# snappergps_1_0_0.net
KiCad netlist of a schematic drawn in EAGLE
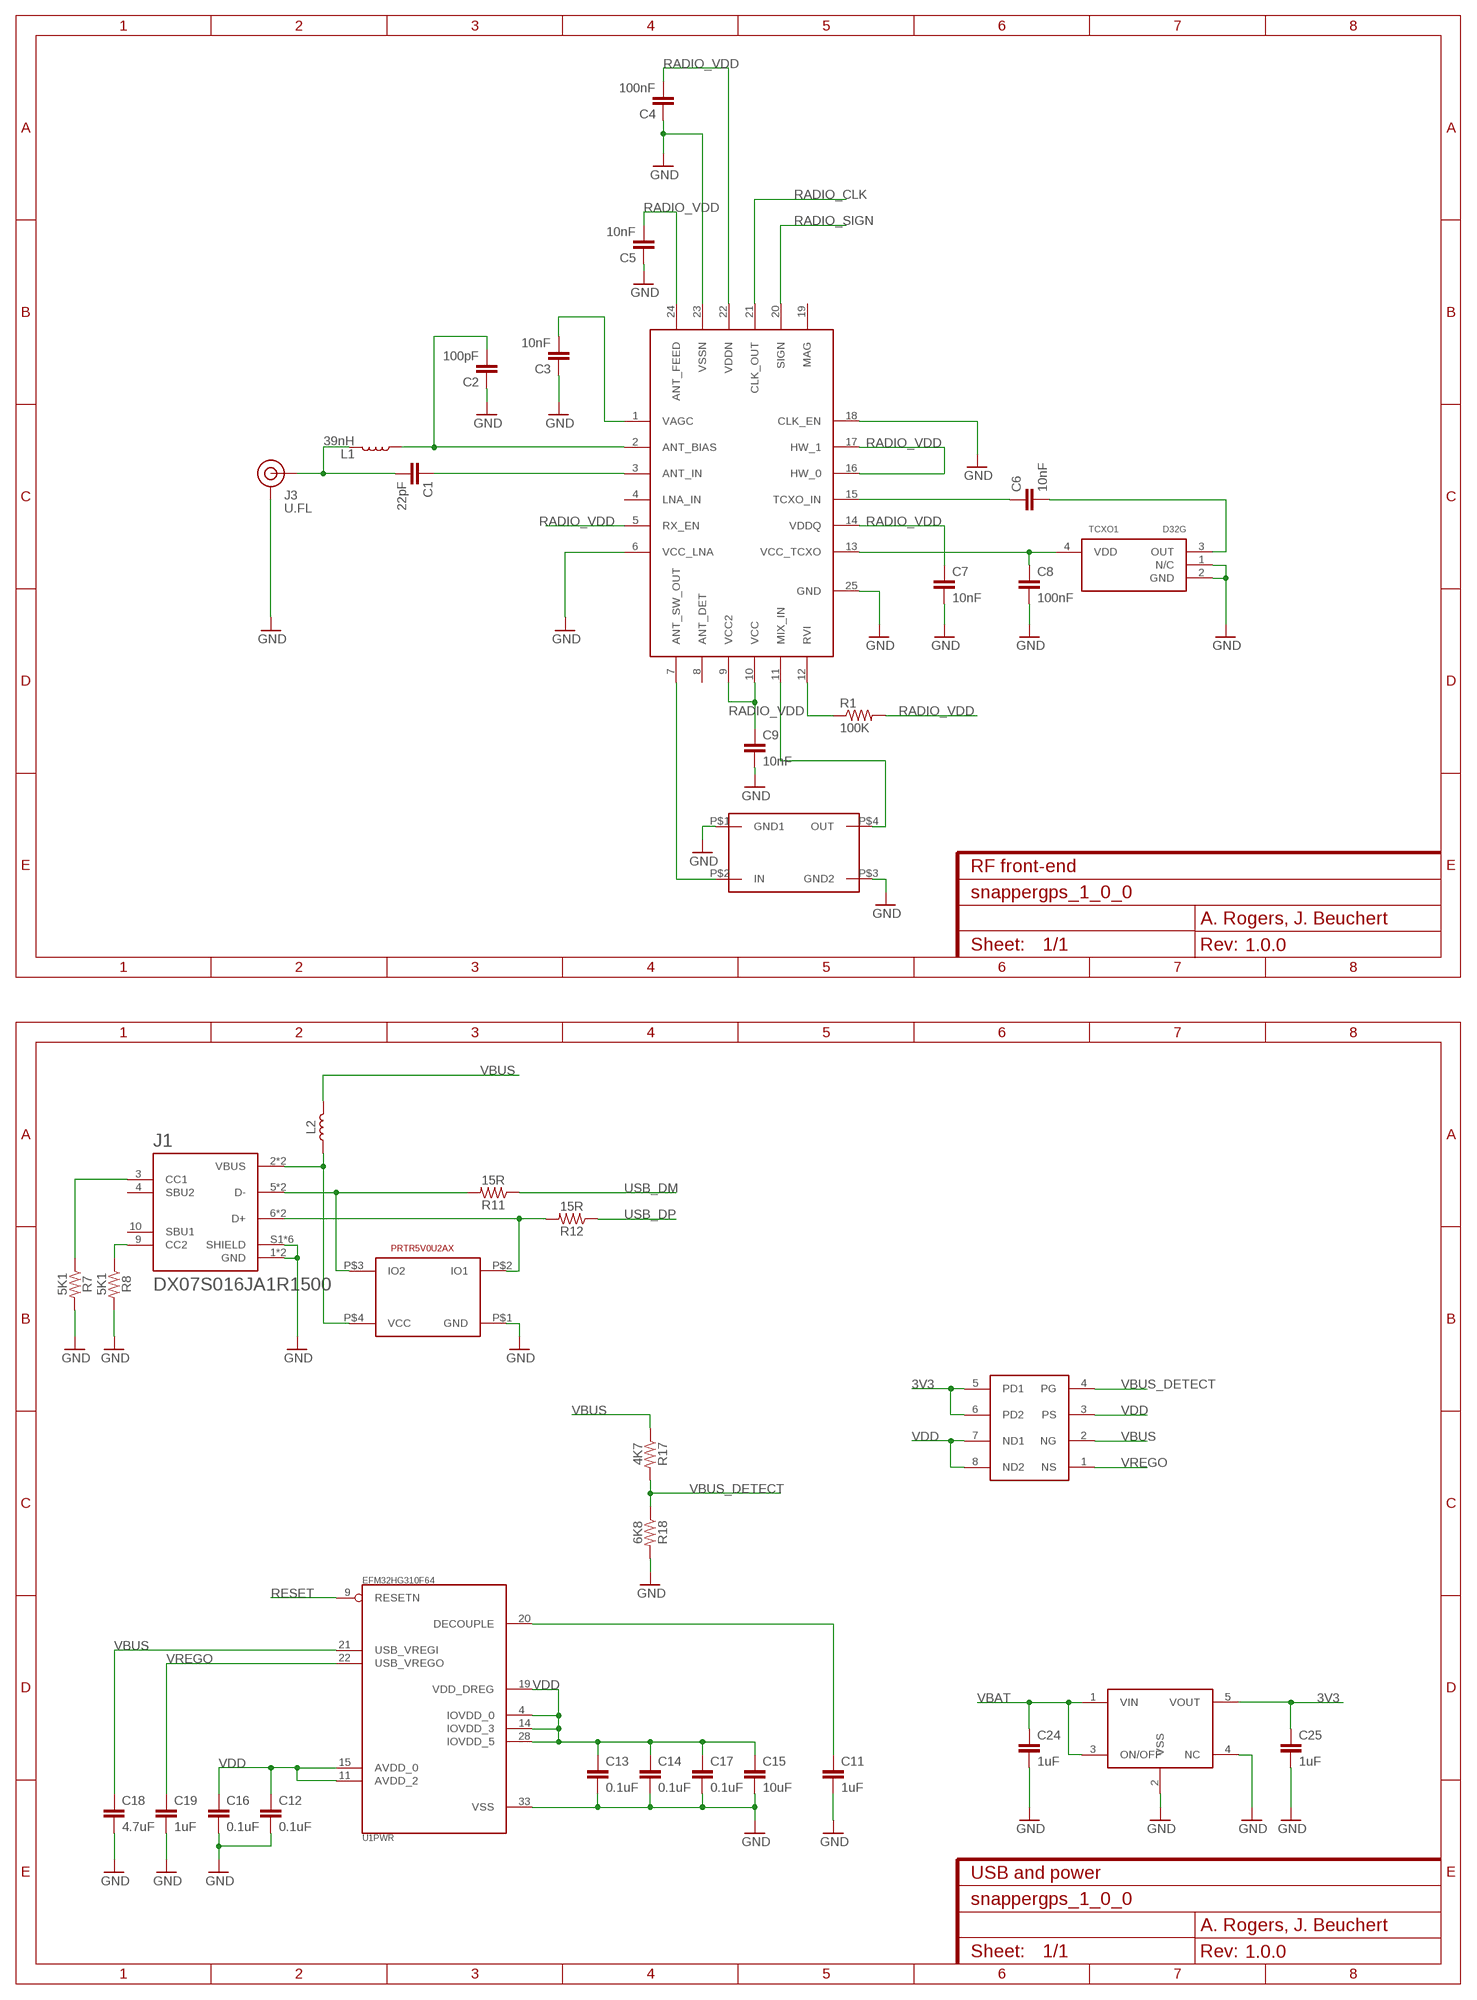
[diagram p0: schematic, sheet 1, part 1 of 2]
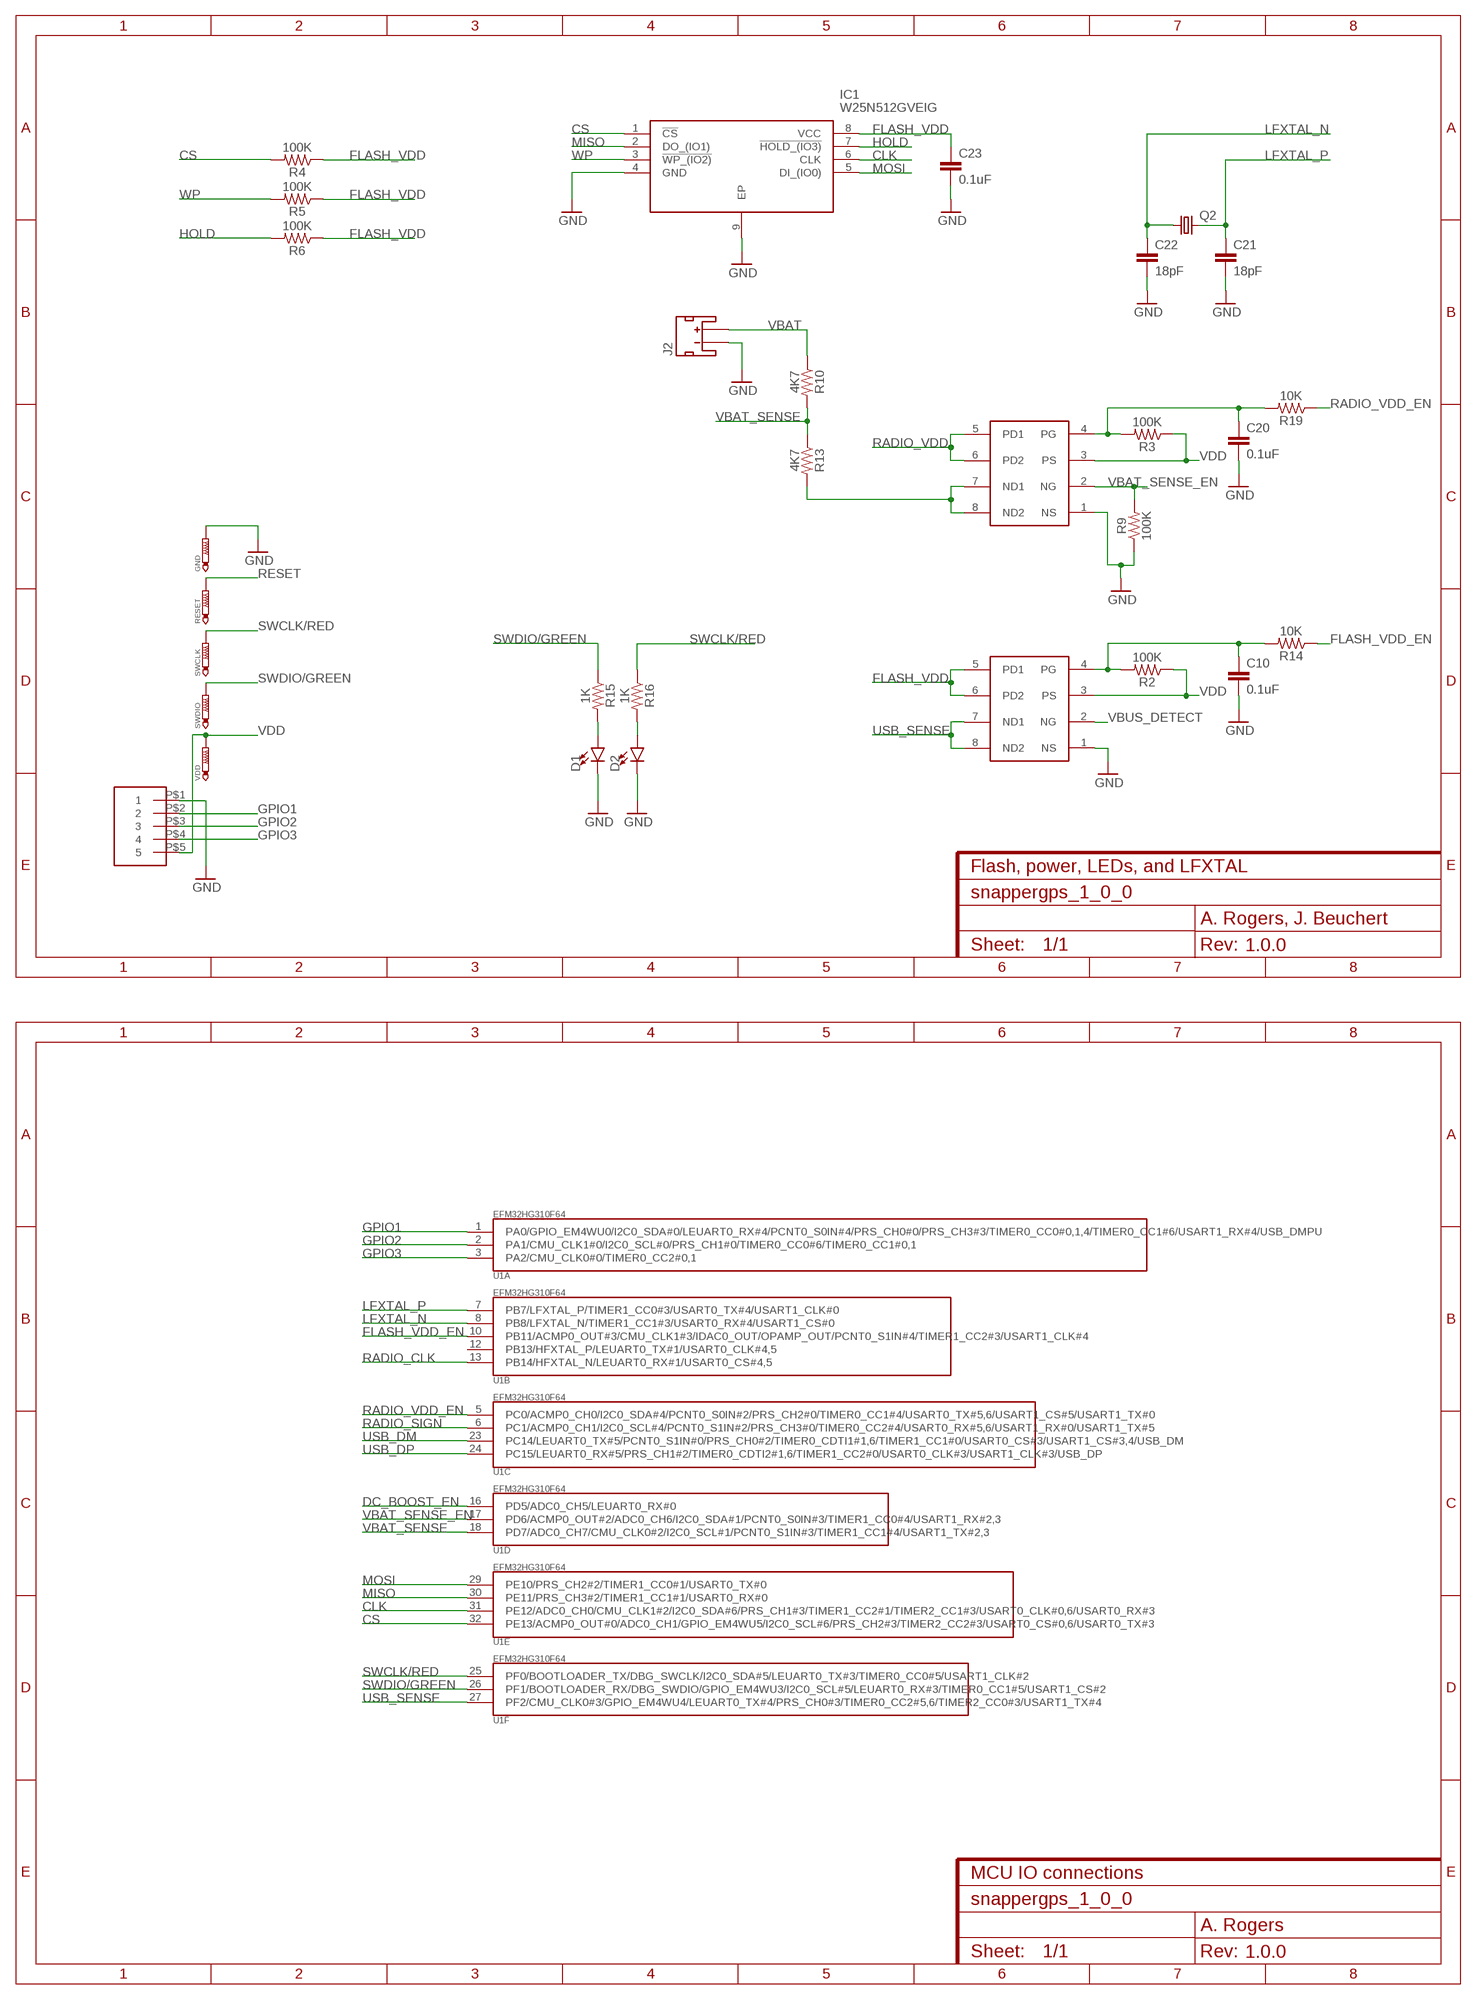
[diagram p1: schematic, sheet 1, part 2 of 2]

(export (version "E")
  (design (tool "Eeschema 10.0.6"))
  (components
    (comp (ref "C1")
      (value "22pF")
      (footprint "eagle-import:0402")
      (libsource (lib "eagle-import") (part "CAPACITOR_0402"))
    )
    (comp (ref "C2")
      (value "100pF")
      (footprint "eagle-import:0402")
      (libsource (lib "eagle-import") (part "CAPACITOR_0402"))
    )
    (comp (ref "C3")
      (value "10nF")
      (footprint "eagle-import:0402")
      (libsource (lib "eagle-import") (part "CAPACITOR_0402"))
    )
    (comp (ref "C4")
      (value "100nF")
      (footprint "eagle-import:0402")
      (libsource (lib "eagle-import") (part "CAPACITOR_0402"))
    )
    (comp (ref "C5")
      (value "10nF")
      (footprint "eagle-import:0402")
      (libsource (lib "eagle-import") (part "CAPACITOR_0402"))
    )
    (comp (ref "C6")
      (value "10nF")
      (footprint "eagle-import:0402")
      (libsource (lib "eagle-import") (part "CAPACITOR_0402"))
    )
    (comp (ref "C7")
      (value "10nF")
      (footprint "eagle-import:0402")
      (libsource (lib "eagle-import") (part "CAPACITOR_0402"))
    )
    (comp (ref "C8")
      (value "100nF")
      (footprint "eagle-import:0402")
      (libsource (lib "eagle-import") (part "CAPACITOR_0402"))
    )
    (comp (ref "C9")
      (value "10nF")
      (footprint "eagle-import:0402")
      (libsource (lib "eagle-import") (part "CAPACITOR_0402"))
    )
    (comp (ref "C10")
      (value "0.1uF")
      (footprint "eagle-import:0402")
      (libsource (lib "eagle-import") (part "CAPACITOR_0402"))
    )
    (comp (ref "C11")
      (value "1uF")
      (footprint "eagle-import:0603")
      (libsource (lib "eagle-import") (part "CAPACITOR_0603"))
    )
    (comp (ref "C12")
      (value "0.1uF")
      (footprint "eagle-import:0402")
      (libsource (lib "eagle-import") (part "CAPACITOR_0402"))
    )
    (comp (ref "C13")
      (value "0.1uF")
      (footprint "eagle-import:0402")
      (libsource (lib "eagle-import") (part "CAPACITOR_0402"))
    )
    (comp (ref "C14")
      (value "0.1uF")
      (footprint "eagle-import:0402")
      (libsource (lib "eagle-import") (part "CAPACITOR_0402"))
    )
    (comp (ref "C15")
      (value "10uF")
      (footprint "eagle-import:0603")
      (libsource (lib "eagle-import") (part "CAPACITOR_0603"))
    )
    (comp (ref "C16")
      (value "0.1uF")
      (footprint "eagle-import:0402")
      (libsource (lib "eagle-import") (part "CAPACITOR_0402"))
    )
    (comp (ref "C17")
      (value "0.1uF")
      (footprint "eagle-import:0402")
      (libsource (lib "eagle-import") (part "CAPACITOR_0402"))
    )
    (comp (ref "C18")
      (value "4.7uF")
      (footprint "eagle-import:0603")
      (libsource (lib "eagle-import") (part "CAPACITOR_0603"))
    )
    (comp (ref "C19")
      (value "1uF")
      (footprint "eagle-import:0603")
      (libsource (lib "eagle-import") (part "CAPACITOR_0603"))
    )
    (comp (ref "C20")
      (value "0.1uF")
      (footprint "eagle-import:0402")
      (libsource (lib "eagle-import") (part "CAPACITOR_0402"))
    )
    (comp (ref "C21")
      (value "18pF")
      (footprint "eagle-import:0402")
      (libsource (lib "eagle-import") (part "CAPACITOR_0402"))
    )
    (comp (ref "C22")
      (value "18pF")
      (footprint "eagle-import:0402")
      (libsource (lib "eagle-import") (part "CAPACITOR_0402"))
    )
    (comp (ref "C23")
      (value "0.1uF")
      (footprint "eagle-import:0402")
      (libsource (lib "eagle-import") (part "CAPACITOR_0402"))
    )
    (comp (ref "C24")
      (value "1uF")
      (footprint "eagle-import:0603")
      (libsource (lib "eagle-import") (part "CAPACITOR_0603"))
    )
    (comp (ref "C25")
      (value "1uF")
      (footprint "eagle-import:0603")
      (libsource (lib "eagle-import") (part "CAPACITOR_0603"))
    )
    (comp (ref "D1")
      (value "LED0603")
      (footprint "eagle-import:LED-0603")
      (libsource (lib "eagle-import") (part "LED0603"))
    )
    (comp (ref "D2")
      (value "LED0603")
      (footprint "eagle-import:LED-0603")
      (libsource (lib "eagle-import") (part "LED0603"))
    )
    (comp (ref "GND")
      (value "PTR1B1,27")
      (footprint "eagle-import:B1,27")
      (libsource (lib "eagle-import") (part "PTR1B1,27"))
    )
    (comp (ref "IC1")
      (value "W25N512GVEIG")
      (footprint "eagle-import:SON127P800X600X80-9N")
      (fields (field (name "MOUSER_PART_NUMBER") "454-W25N512GVEIG"))
      (libsource (lib "eagle-import") (part "W25N512GVEIG"))
    )
    (comp (ref "J1")
      (value "DX07S016JA1R1500")
      (footprint "eagle-import:JAE_DX07S016JA1R1500")
      (fields (field (name "MF") "JAE Electronics"))
      (libsource (lib "eagle-import") (part "DX07S016JA1R1500"))
    )
    (comp (ref "J2")
      (value "JST_2MM_MALE")
      (footprint "eagle-import:JST-2-SMD")
      (libsource (lib "eagle-import") (part "JST_2MM_MALE"))
    )
    (comp (ref "J3")
      (value "U.FL")
      (footprint "eagle-import:U.FL")
      (libsource (lib "eagle-import") (part "UFL-CONNECTOR"))
    )
    (comp (ref "L1")
      (value "39nH")
      (footprint "eagle-import:0402")
      (libsource (lib "eagle-import") (part "INDUCTOR"))
    )
    (comp (ref "L2")
      (value "INDUCTOR")
      (footprint "eagle-import:0402")
      (libsource (lib "eagle-import") (part "INDUCTOR"))
    )
    (comp (ref "Q1")
      (value "TT8M1TRAMANDA")
      (footprint "eagle-import:AMANDA_TSST8")
      (libsource (lib "eagle-import") (part "TT8M1TRAMANDA"))
    )
    (comp (ref "Q2")
      (value "CRYSTAL_JTX310")
      (footprint "eagle-import:3.2X1.5")
      (libsource (lib "eagle-import") (part "CRYSTAL_JTX310"))
    )
    (comp (ref "Q3")
      (value "TT8M1TRAMANDA")
      (footprint "eagle-import:AMANDA_TSST8")
      (libsource (lib "eagle-import") (part "TT8M1TRAMANDA"))
    )
    (comp (ref "Q4")
      (value "TT8M1TRAMANDA")
      (footprint "eagle-import:AMANDA_TSST8")
      (libsource (lib "eagle-import") (part "TT8M1TRAMANDA"))
    )
    (comp (ref "R1")
      (value "100K")
      (footprint "eagle-import:0402")
      (libsource (lib "eagle-import") (part "RESISTOR_0402"))
    )
    (comp (ref "R2")
      (value "100K")
      (footprint "eagle-import:0402")
      (libsource (lib "eagle-import") (part "RESISTOR_0402"))
    )
    (comp (ref "R3")
      (value "100K")
      (footprint "eagle-import:0402")
      (libsource (lib "eagle-import") (part "RESISTOR_0402"))
    )
    (comp (ref "R4")
      (value "100K")
      (footprint "eagle-import:0402")
      (libsource (lib "eagle-import") (part "RESISTOR_0402"))
    )
    (comp (ref "R5")
      (value "100K")
      (footprint "eagle-import:0402")
      (libsource (lib "eagle-import") (part "RESISTOR_0402"))
    )
    (comp (ref "R6")
      (value "100K")
      (footprint "eagle-import:0402")
      (libsource (lib "eagle-import") (part "RESISTOR_0402"))
    )
    (comp (ref "R7")
      (value "5K1")
      (footprint "eagle-import:0402")
      (libsource (lib "eagle-import") (part "RESISTOR_0402"))
    )
    (comp (ref "R8")
      (value "5K1")
      (footprint "eagle-import:0402")
      (libsource (lib "eagle-import") (part "RESISTOR_0402"))
    )
    (comp (ref "R9")
      (value "100K")
      (footprint "eagle-import:0402")
      (libsource (lib "eagle-import") (part "RESISTOR_0402"))
    )
    (comp (ref "R10")
      (value "4K7")
      (footprint "eagle-import:0402")
      (libsource (lib "eagle-import") (part "RESISTOR_0402"))
    )
    (comp (ref "R11")
      (value "15R")
      (footprint "eagle-import:0402")
      (libsource (lib "eagle-import") (part "RESISTOR_0402"))
    )
    (comp (ref "R12")
      (value "15R")
      (footprint "eagle-import:0402")
      (libsource (lib "eagle-import") (part "RESISTOR_0402"))
    )
    (comp (ref "R13")
      (value "4K7")
      (footprint "eagle-import:0402")
      (libsource (lib "eagle-import") (part "RESISTOR_0402"))
    )
    (comp (ref "R14")
      (value "10K")
      (footprint "eagle-import:0402")
      (libsource (lib "eagle-import") (part "RESISTOR_0402"))
    )
    (comp (ref "R15")
      (value "1K")
      (footprint "eagle-import:0402")
      (libsource (lib "eagle-import") (part "RESISTOR_0402"))
    )
    (comp (ref "R16")
      (value "1K")
      (footprint "eagle-import:0402")
      (libsource (lib "eagle-import") (part "RESISTOR_0402"))
    )
    (comp (ref "R17")
      (value "4K7")
      (footprint "eagle-import:0402")
      (libsource (lib "eagle-import") (part "RESISTOR_0402"))
    )
    (comp (ref "R18")
      (value "6K8")
      (footprint "eagle-import:0402")
      (libsource (lib "eagle-import") (part "RESISTOR_0402"))
    )
    (comp (ref "R19")
      (value "10K")
      (footprint "eagle-import:0402")
      (libsource (lib "eagle-import") (part "RESISTOR_0402"))
    )
    (comp (ref "RESET")
      (value "PTR1B1,27")
      (footprint "eagle-import:B1,27")
      (libsource (lib "eagle-import") (part "PTR1B1,27"))
    )
    (comp (ref "SAW1")
      (value "SAW_FILTER")
      (footprint "eagle-import:SAW_FILTER")
      (libsource (lib "eagle-import") (part "SAW_FILTER"))
    )
    (comp (ref "SWCLK")
      (value "PTR1B1,27")
      (footprint "eagle-import:B1,27")
      (libsource (lib "eagle-import") (part "PTR1B1,27"))
    )
    (comp (ref "SWDIO")
      (value "PTR1B1,27")
      (footprint "eagle-import:B1,27")
      (libsource (lib "eagle-import") (part "PTR1B1,27"))
    )
    (comp (ref "TCXO1")
      (value "D32G")
      (footprint "eagle-import:D32G")
      (libsource (lib "eagle-import") (part "D32G"))
    )
    (comp (ref "U1")
      (value "EFM32HG310F64")
      (footprint "eagle-import:QFN32")
      (libsource (lib "eagle-import") (part "EFM32HG310F64"))
    )
    (comp (ref "U2")
      (value "RF_CIRCUIT-SE4150L")
      (footprint "eagle-import:QFN50P400X400X90-25N")
      (libsource (lib "eagle-import") (part "RF_CIRCUIT-SE4150L"))
    )
    (comp (ref "U3")
      (value "TVS_DIODE-PRTR5V0U2AX")
      (footprint "eagle-import:TVS_DIODE-PRTR5V0U2AX")
      (libsource (lib "eagle-import") (part "TVS_DIODE-PRTR5V0U2AX"))
    )
    (comp (ref "U4")
      (value "S-1318D33-M5T1U4")
      (footprint "eagle-import:SOT95P280X145-5N")
      (libsource (lib "eagle-import") (part "S-1318D33-M5T1U4"))
    )
    (comp (ref "U5")
      (value "ALEX_CONN5")
      (footprint "eagle-import:ALEX_CONN5")
      (libsource (lib "eagle-import") (part "ALEX_CONN5"))
    )
    (comp (ref "VDD")
      (value "PTR1B1,27")
      (footprint "eagle-import:B1,27")
      (libsource (lib "eagle-import") (part "PTR1B1,27"))
    )
  )
  (nets
    (net (code "1") (name "/3V3") (class "Default")
      (node (ref "C25") (pin "1") (pinfunction "1_1") (pintype "passive"))
      (node (ref "Q4") (pin "5") (pinfunction "PD1_5") (pintype "bidirectional"))
      (node (ref "Q4") (pin "6") (pinfunction "PD2_6") (pintype "bidirectional"))
      (node (ref "U4") (pin "5") (pinfunction "VOUT_5") (pintype "bidirectional"))
    )
    (net (code "2") (name "/CLK") (class "Default")
      (node (ref "IC1") (pin "6") (pinfunction "CLK_6") (pintype "bidirectional"))
      (node (ref "U1") (pin "31") (pinfunction "PE12/ADC0_CH0/CMU_CLK1#2/I2C0_SDA#6/PRS_CH1#3/TIMER1_CC2#1/TIMER2_CC1#3/USART0_CLK#0,6/USART0_RX#3_31") (pintype "bidirectional"))
    )
    (net (code "3") (name "/CS") (class "Default")
      (node (ref "IC1") (pin "1") (pinfunction "~{CS}_1") (pintype "bidirectional"))
      (node (ref "R4") (pin "2") (pinfunction "2_2") (pintype "passive"))
      (node (ref "U1") (pin "32") (pinfunction "PE13/ACMP0_OUT#0/ADC0_CH1/GPIO_EM4WU5/I2C0_SCL#6/PRS_CH2#3/TIMER2_CC2#3/USART0_CS#0,6/USART0_TX#3_32") (pintype "bidirectional"))
    )
    (net (code "4") (name "/DC_BOOST_EN") (class "Default")
      (node (ref "U1") (pin "16") (pinfunction "PD5/ADC0_CH5/LEUART0_RX#0_16") (pintype "bidirectional"))
    )
    (net (code "5") (name "/FLASH_VDD") (class "Default")
      (node (ref "C23") (pin "1") (pinfunction "1_1") (pintype "passive"))
      (node (ref "IC1") (pin "8") (pinfunction "VCC_8") (pintype "bidirectional"))
      (node (ref "Q3") (pin "5") (pinfunction "PD1_5") (pintype "bidirectional"))
      (node (ref "Q3") (pin "6") (pinfunction "PD2_6") (pintype "bidirectional"))
      (node (ref "R4") (pin "1") (pinfunction "1_1") (pintype "passive"))
      (node (ref "R5") (pin "1") (pinfunction "1_1") (pintype "passive"))
      (node (ref "R6") (pin "1") (pinfunction "1_1") (pintype "passive"))
    )
    (net (code "6") (name "/FLASH_VDD_EN") (class "Default")
      (node (ref "R14") (pin "1") (pinfunction "1_1") (pintype "passive"))
      (node (ref "U1") (pin "10") (pinfunction "PB11/ACMP0_OUT#3/CMU_CLK1#3/IDAC0_OUT/OPAMP_OUT/PCNT0_S1IN#4/TIMER1_CC2#3/USART1_CLK#4_10") (pintype "bidirectional"))
    )
    (net (code "7") (name "/GPIO1") (class "Default")
      (node (ref "U1") (pin "1") (pinfunction "PA0/GPIO_EM4WU0/I2C0_SDA#0/LEUART0_RX#4/PCNT0_S0IN#4/PRS_CH0#0/PRS_CH3#3/TIMER0_CC0#0,1,4/TIMER0_CC1#6/USART1_RX#4/USB_DMPU_1") (pintype "bidirectional"))
      (node (ref "U5") (pin "P$2") (pinfunction "2_P$2") (pintype "bidirectional"))
    )
    (net (code "8") (name "/GPIO2") (class "Default")
      (node (ref "U1") (pin "2") (pinfunction "PA1/CMU_CLK1#0/I2C0_SCL#0/PRS_CH1#0/TIMER0_CC0#6/TIMER0_CC1#0,1_2") (pintype "bidirectional"))
      (node (ref "U5") (pin "P$3") (pinfunction "3_P$3") (pintype "bidirectional"))
    )
    (net (code "9") (name "/GPIO3") (class "Default")
      (node (ref "U1") (pin "3") (pinfunction "PA2/CMU_CLK0#0/TIMER0_CC2#0,1_3") (pintype "bidirectional"))
      (node (ref "U5") (pin "P$4") (pinfunction "4_P$4") (pintype "bidirectional"))
    )
    (net (code "10") (name "/HOLD") (class "Default")
      (node (ref "IC1") (pin "7") (pinfunction "~{HOLD_(IO3})_7") (pintype "bidirectional"))
      (node (ref "R6") (pin "2") (pinfunction "2_2") (pintype "passive"))
    )
    (net (code "11") (name "/LFXTAL_N") (class "Default")
      (node (ref "C22") (pin "1") (pinfunction "1_1") (pintype "passive"))
      (node (ref "Q2") (pin "1") (pinfunction "1_1") (pintype "passive"))
      (node (ref "U1") (pin "8") (pinfunction "PB8/LFXTAL_N/TIMER1_CC1#3/USART0_RX#4/USART1_CS#0_8") (pintype "bidirectional"))
    )
    (net (code "12") (name "/LFXTAL_P") (class "Default")
      (node (ref "C21") (pin "1") (pinfunction "1_1") (pintype "passive"))
      (node (ref "Q2") (pin "2") (pinfunction "2_2") (pintype "passive"))
      (node (ref "U1") (pin "7") (pinfunction "PB7/LFXTAL_P/TIMER1_CC0#3/USART0_TX#4/USART1_CLK#0_7") (pintype "bidirectional"))
    )
    (net (code "13") (name "/MISO") (class "Default")
      (node (ref "IC1") (pin "2") (pinfunction "DO_(IO1)_2") (pintype "bidirectional"))
      (node (ref "U1") (pin "30") (pinfunction "PE11/PRS_CH3#2/TIMER1_CC1#1/USART0_RX#0_30") (pintype "bidirectional"))
    )
    (net (code "14") (name "/MOSI") (class "Default")
      (node (ref "IC1") (pin "5") (pinfunction "DI_(IO0)_5") (pintype "bidirectional"))
      (node (ref "U1") (pin "29") (pinfunction "PE10/PRS_CH2#2/TIMER1_CC0#1/USART0_TX#0_29") (pintype "bidirectional"))
    )
    (net (code "15") (name "/RADIO_CLK") (class "Default")
      (node (ref "U1") (pin "13") (pinfunction "PB14/HFXTAL_N/LEUART0_RX#1/USART0_CS#4,5_13") (pintype "bidirectional"))
      (node (ref "U2") (pin "21") (pinfunction "CLK_OUT_21") (pintype "bidirectional"))
    )
    (net (code "16") (name "/RADIO_SIGN") (class "Default")
      (node (ref "U1") (pin "6") (pinfunction "PC1/ACMP0_CH1/I2C0_SCL#4/PCNT0_S1IN#2/PRS_CH3#0/TIMER0_CC2#4/USART0_RX#5,6/USART1_RX#0/USART1_TX#5_6") (pintype "bidirectional"))
      (node (ref "U2") (pin "20") (pinfunction "SIGN_20") (pintype "bidirectional"))
    )
    (net (code "17") (name "/RADIO_VDD") (class "Default")
      (node (ref "C4") (pin "2") (pinfunction "2_2") (pintype "passive"))
      (node (ref "C5") (pin "2") (pinfunction "2_2") (pintype "passive"))
      (node (ref "C7") (pin "1") (pinfunction "1_1") (pintype "passive"))
      (node (ref "C9") (pin "1") (pinfunction "1_1") (pintype "passive"))
      (node (ref "Q1") (pin "5") (pinfunction "PD1_5") (pintype "bidirectional"))
      (node (ref "Q1") (pin "6") (pinfunction "PD2_6") (pintype "bidirectional"))
      (node (ref "R1") (pin "2") (pinfunction "2_2") (pintype "passive"))
      (node (ref "U2") (pin "10") (pinfunction "VCC_10") (pintype "bidirectional"))
      (node (ref "U2") (pin "14") (pinfunction "VDDQ_14") (pintype "bidirectional"))
      (node (ref "U2") (pin "16") (pinfunction "HW_0_16") (pintype "bidirectional"))
      (node (ref "U2") (pin "17") (pinfunction "HW_1_17") (pintype "bidirectional"))
      (node (ref "U2") (pin "22") (pinfunction "VDDN_22") (pintype "bidirectional"))
      (node (ref "U2") (pin "24") (pinfunction "ANT_FEED_24") (pintype "bidirectional"))
      (node (ref "U2") (pin "5") (pinfunction "RX_EN_5") (pintype "bidirectional"))
      (node (ref "U2") (pin "9") (pinfunction "VCC2_9") (pintype "bidirectional"))
    )
    (net (code "18") (name "/RADIO_VDD_EN") (class "Default")
      (node (ref "R19") (pin "1") (pinfunction "1_1") (pintype "passive"))
      (node (ref "U1") (pin "5") (pinfunction "PC0/ACMP0_CH0/I2C0_SDA#4/PCNT0_S0IN#2/PRS_CH2#0/TIMER0_CC1#4/USART0_TX#5,6/USART1_CS#5/USART1_TX#0_5") (pintype "bidirectional"))
    )
    (net (code "19") (name "/RESET") (class "Default")
      (node (ref "RESET") (pin "TP") (pinfunction "TP_TP") (pintype "input"))
      (node (ref "U1") (pin "9") (pinfunction "RESETN_9") (pintype "passive"))
    )
    (net (code "20") (name "/SWCLK{slash}RED") (class "Default")
      (node (ref "R16") (pin "1") (pinfunction "1_1") (pintype "passive"))
      (node (ref "SWCLK") (pin "TP") (pinfunction "TP_TP") (pintype "input"))
      (node (ref "U1") (pin "25") (pinfunction "PF0/BOOTLOADER_TX/DBG_SWCLK/I2C0_SDA#5/LEUART0_TX#3/TIMER0_CC0#5/USART1_CLK#2_25") (pintype "bidirectional"))
    )
    (net (code "21") (name "/SWDIO{slash}GREEN") (class "Default")
      (node (ref "R15") (pin "1") (pinfunction "1_1") (pintype "passive"))
      (node (ref "SWDIO") (pin "TP") (pinfunction "TP_TP") (pintype "input"))
      (node (ref "U1") (pin "26") (pinfunction "PF1/BOOTLOADER_RX/DBG_SWDIO/GPIO_EM4WU3/I2C0_SCL#5/LEUART0_RX#3/TIMER0_CC1#5/USART1_CS#2_26") (pintype "bidirectional"))
    )
    (net (code "22") (name "/USB_DM") (class "Default")
      (node (ref "R11") (pin "1") (pinfunction "1_1") (pintype "passive"))
      (node (ref "U1") (pin "23") (pinfunction "PC14/LEUART0_TX#5/PCNT0_S1IN#0/PRS_CH0#2/TIMER0_CDTI1#1,6/TIMER1_CC1#0/USART0_CS#3/USART1_CS#3,4/USB_DM_23") (pintype "bidirectional"))
    )
    (net (code "23") (name "/USB_DP") (class "Default")
      (node (ref "R12") (pin "1") (pinfunction "1_1") (pintype "passive"))
      (node (ref "U1") (pin "24") (pinfunction "PC15/LEUART0_RX#5/PRS_CH1#2/TIMER0_CDTI2#1,6/TIMER1_CC2#0/USART0_CLK#3/USART1_CLK#3/USB_DP_24") (pintype "bidirectional"))
    )
    (net (code "24") (name "/USB_SENSE") (class "Default")
      (node (ref "Q3") (pin "7") (pinfunction "ND1_7") (pintype "bidirectional"))
      (node (ref "Q3") (pin "8") (pinfunction "ND2_8") (pintype "bidirectional"))
      (node (ref "U1") (pin "27") (pinfunction "PF2/CMU_CLK0#3/GPIO_EM4WU4/LEUART0_TX#4/PRS_CH0#3/TIMER0_CC2#5,6/TIMER2_CC0#3/USART1_TX#4_27") (pintype "bidirectional"))
    )
    (net (code "25") (name "/VBAT") (class "Default")
      (node (ref "C24") (pin "1") (pinfunction "1_1") (pintype "passive"))
      (node (ref "J2") (pin "2") (pinfunction "+_2") (pintype "bidirectional"))
      (node (ref "R10") (pin "1") (pinfunction "1_1") (pintype "passive"))
      (node (ref "U4") (pin "1") (pinfunction "VIN_1") (pintype "bidirectional"))
      (node (ref "U4") (pin "3") (pinfunction "ON/OFF_3") (pintype "bidirectional"))
    )
    (net (code "26") (name "/VBAT_SENSE") (class "Default")
      (node (ref "R10") (pin "2") (pinfunction "2_2") (pintype "passive"))
      (node (ref "R13") (pin "1") (pinfunction "1_1") (pintype "passive"))
      (node (ref "U1") (pin "18") (pinfunction "PD7/ADC0_CH7/CMU_CLK0#2/I2C0_SCL#1/PCNT0_S1IN#3/TIMER1_CC1#4/USART1_TX#2,3_18") (pintype "bidirectional"))
    )
    (net (code "27") (name "/VBAT_SENSE_EN") (class "Default")
      (node (ref "Q1") (pin "2") (pinfunction "NG_2") (pintype "bidirectional"))
      (node (ref "R9") (pin "2") (pinfunction "2_2") (pintype "passive"))
      (node (ref "U1") (pin "17") (pinfunction "PD6/ACMP0_OUT#2/ADC0_CH6/I2C0_SDA#1/PCNT0_S0IN#3/TIMER1_CC0#4/USART1_RX#2,3_17") (pintype "bidirectional"))
    )
    (net (code "28") (name "/VBUS") (class "Default")
      (node (ref "C18") (pin "1") (pinfunction "1_1") (pintype "passive"))
      (node (ref "L2") (pin "2") (pinfunction "2_2") (pintype "passive"))
      (node (ref "Q4") (pin "2") (pinfunction "NG_2") (pintype "bidirectional"))
      (node (ref "R17") (pin "1") (pinfunction "1_1") (pintype "passive"))
      (node (ref "U1") (pin "21") (pinfunction "USB_VREGI_21") (pintype "power_in"))
    )
    (net (code "29") (name "/VBUS_DETECT") (class "Default")
      (node (ref "Q3") (pin "2") (pinfunction "NG_2") (pintype "bidirectional"))
      (node (ref "Q4") (pin "4") (pinfunction "PG_4") (pintype "bidirectional"))
      (node (ref "R17") (pin "2") (pinfunction "2_2") (pintype "passive"))
      (node (ref "R18") (pin "1") (pinfunction "1_1") (pintype "passive"))
    )
    (net (code "30") (name "/VDD") (class "Default")
      (node (ref "C12") (pin "1") (pinfunction "1_1") (pintype "passive"))
      (node (ref "C13") (pin "1") (pinfunction "1_1") (pintype "passive"))
      (node (ref "C14") (pin "1") (pinfunction "1_1") (pintype "passive"))
      (node (ref "C15") (pin "1") (pinfunction "1_1") (pintype "passive"))
      (node (ref "C16") (pin "1") (pinfunction "1_1") (pintype "passive"))
      (node (ref "C17") (pin "1") (pinfunction "1_1") (pintype "passive"))
      (node (ref "Q1") (pin "3") (pinfunction "PS_3") (pintype "bidirectional"))
      (node (ref "Q3") (pin "3") (pinfunction "PS_3") (pintype "bidirectional"))
      (node (ref "Q4") (pin "3") (pinfunction "PS_3") (pintype "bidirectional"))
      (node (ref "Q4") (pin "7") (pinfunction "ND1_7") (pintype "bidirectional"))
      (node (ref "Q4") (pin "8") (pinfunction "ND2_8") (pintype "bidirectional"))
      (node (ref "R2") (pin "1") (pinfunction "1_1") (pintype "passive"))
      (node (ref "R3") (pin "1") (pinfunction "1_1") (pintype "passive"))
      (node (ref "U1") (pin "11") (pinfunction "AVDD_2_11") (pintype "power_in"))
      (node (ref "U1") (pin "14") (pinfunction "IOVDD_3_14") (pintype "power_in"))
      (node (ref "U1") (pin "15") (pinfunction "AVDD_0_15") (pintype "power_in"))
      (node (ref "U1") (pin "19") (pinfunction "VDD_DREG_19") (pintype "power_in"))
      (node (ref "U1") (pin "28") (pinfunction "IOVDD_5_28") (pintype "power_in"))
      (node (ref "U1") (pin "4") (pinfunction "IOVDD_0_4") (pintype "power_in"))
      (node (ref "U5") (pin "P$5") (pinfunction "5_P$5") (pintype "bidirectional"))
      (node (ref "VDD") (pin "TP") (pinfunction "TP_TP") (pintype "input"))
    )
    (net (code "31") (name "/VREGO") (class "Default")
      (node (ref "C19") (pin "1") (pinfunction "1_1") (pintype "passive"))
      (node (ref "Q4") (pin "1") (pinfunction "NS_1") (pintype "bidirectional"))
      (node (ref "U1") (pin "22") (pinfunction "USB_VREGO_22") (pintype "power_in"))
    )
    (net (code "32") (name "/WP") (class "Default")
      (node (ref "IC1") (pin "3") (pinfunction "~{WP_(IO2})_3") (pintype "bidirectional"))
      (node (ref "R5") (pin "2") (pinfunction "2_2") (pintype "passive"))
    )
    (net (code "33") (name "GND") (class "Default")
      (node (ref "C10") (pin "2") (pinfunction "2_2") (pintype "passive"))
      (node (ref "C11") (pin "2") (pinfunction "2_2") (pintype "passive"))
      (node (ref "C12") (pin "2") (pinfunction "2_2") (pintype "passive"))
      (node (ref "C13") (pin "2") (pinfunction "2_2") (pintype "passive"))
      (node (ref "C14") (pin "2") (pinfunction "2_2") (pintype "passive"))
      (node (ref "C15") (pin "2") (pinfunction "2_2") (pintype "passive"))
      (node (ref "C16") (pin "2") (pinfunction "2_2") (pintype "passive"))
      (node (ref "C17") (pin "2") (pinfunction "2_2") (pintype "passive"))
      (node (ref "C18") (pin "2") (pinfunction "2_2") (pintype "passive"))
      (node (ref "C19") (pin "2") (pinfunction "2_2") (pintype "passive"))
      (node (ref "C2") (pin "1") (pinfunction "1_1") (pintype "passive"))
      (node (ref "C20") (pin "2") (pinfunction "2_2") (pintype "passive"))
      (node (ref "C21") (pin "2") (pinfunction "2_2") (pintype "passive"))
      (node (ref "C22") (pin "2") (pinfunction "2_2") (pintype "passive"))
      (node (ref "C23") (pin "2") (pinfunction "2_2") (pintype "passive"))
      (node (ref "C24") (pin "2") (pinfunction "2_2") (pintype "passive"))
      (node (ref "C25") (pin "2") (pinfunction "2_2") (pintype "passive"))
      (node (ref "C3") (pin "1") (pinfunction "1_1") (pintype "passive"))
      (node (ref "C4") (pin "1") (pinfunction "1_1") (pintype "passive"))
      (node (ref "C5") (pin "1") (pinfunction "1_1") (pintype "passive"))
      (node (ref "C7") (pin "2") (pinfunction "2_2") (pintype "passive"))
      (node (ref "C8") (pin "2") (pinfunction "2_2") (pintype "passive"))
      (node (ref "C9") (pin "2") (pinfunction "2_2") (pintype "passive"))
      (node (ref "D1") (pin "C") (pinfunction "C_C") (pintype "passive"))
      (node (ref "D2") (pin "C") (pinfunction "C_C") (pintype "passive"))
      (node (ref "GND") (pin "TP") (pinfunction "TP_TP") (pintype "input"))
      (node (ref "IC1") (pin "4") (pinfunction "GND_4") (pintype "bidirectional"))
      (node (ref "IC1") (pin "9") (pinfunction "EP_9") (pintype "bidirectional"))
      (node (ref "J1") (pin "1") (pinfunction "GND_1") (pintype "power_in"))
      (node (ref "J1") (pin "12") (pinfunction "GND_12") (pintype "power_in"))
      (node (ref "J1") (pin "S1") (pinfunction "SHIELD_S1") (pintype "passive"))
      (node (ref "J1") (pin "S2") (pinfunction "SHIELD_S2") (pintype "passive"))
      (node (ref "J1") (pin "S3") (pinfunction "SHIELD_S3") (pintype "passive"))
      (node (ref "J1") (pin "S4") (pinfunction "SHIELD_S4") (pintype "passive"))
      (node (ref "J1") (pin "S5") (pinfunction "SHIELD_S5") (pintype "passive"))
      (node (ref "J1") (pin "S6") (pinfunction "SHIELD_S6") (pintype "passive"))
      (node (ref "J2") (pin "1") (pinfunction "-_1") (pintype "bidirectional"))
      (node (ref "J3") (pin "1") (pinfunction "GND_1") (pintype "bidirectional"))
      (node (ref "J3") (pin "2") (pinfunction "GND_2") (pintype "bidirectional"))
      (node (ref "Q1") (pin "1") (pinfunction "NS_1") (pintype "bidirectional"))
      (node (ref "Q3") (pin "1") (pinfunction "NS_1") (pintype "bidirectional"))
      (node (ref "R18") (pin "2") (pinfunction "2_2") (pintype "passive"))
      (node (ref "R7") (pin "2") (pinfunction "2_2") (pintype "passive"))
      (node (ref "R8") (pin "2") (pinfunction "2_2") (pintype "passive"))
      (node (ref "R9") (pin "1") (pinfunction "1_1") (pintype "passive"))
      (node (ref "SAW1") (pin "P$1") (pinfunction "GND1_P$1") (pintype "bidirectional"))
      (node (ref "SAW1") (pin "P$3") (pinfunction "GND2_P$3") (pintype "bidirectional"))
      (node (ref "TCXO1") (pin "1") (pinfunction "N/C_1") (pintype "bidirectional"))
      (node (ref "TCXO1") (pin "2") (pinfunction "GND_2") (pintype "bidirectional"))
      (node (ref "U1") (pin "33") (pinfunction "VSS_33") (pintype "power_in"))
      (node (ref "U2") (pin "18") (pinfunction "CLK_EN_18") (pintype "bidirectional"))
      (node (ref "U2") (pin "23") (pinfunction "VSSN_23") (pintype "bidirectional"))
      (node (ref "U2") (pin "25") (pinfunction "GND_25") (pintype "bidirectional"))
      (node (ref "U2") (pin "6") (pinfunction "VCC_LNA_6") (pintype "bidirectional"))
      (node (ref "U3") (pin "P$1") (pinfunction "GND_P$1") (pintype "bidirectional"))
      (node (ref "U4") (pin "2") (pinfunction "VSS_2") (pintype "bidirectional"))
      (node (ref "U4") (pin "4") (pinfunction "NC_4") (pintype "bidirectional"))
      (node (ref "U5") (pin "P$1") (pinfunction "1_P$1") (pintype "bidirectional"))
    )
    (net (code "34") (name "Net-(D1-PadA)") (class "Default")
      (node (ref "D1") (pin "A") (pinfunction "A_A") (pintype "passive"))
      (node (ref "R15") (pin "2") (pinfunction "2_2") (pintype "passive"))
    )
    (net (code "35") (name "Net-(D2-PadA)") (class "Default")
      (node (ref "D2") (pin "A") (pinfunction "A_A") (pintype "passive"))
      (node (ref "R16") (pin "2") (pinfunction "2_2") (pintype "passive"))
    )
    (net (code "36") (name "Net-(J1-CC1)") (class "Default")
      (node (ref "J1") (pin "3") (pinfunction "CC1_3") (pintype "passive"))
      (node (ref "R7") (pin "1") (pinfunction "1_1") (pintype "passive"))
    )
    (net (code "37") (name "Net-(J1-CC2)") (class "Default")
      (node (ref "J1") (pin "9") (pinfunction "CC2_9") (pintype "passive"))
      (node (ref "R8") (pin "1") (pinfunction "1_1") (pintype "passive"))
    )
    (net (code "38") (name "Net-(J3-SIGNAL)") (class "Default")
      (node (ref "C1") (pin "2") (pinfunction "2_2") (pintype "passive"))
      (node (ref "J3") (pin "FEED") (pinfunction "SIGNAL_FEED") (pintype "bidirectional"))
      (node (ref "L1") (pin "2") (pinfunction "2_2") (pintype "passive"))
    )
    (net (code "39") (name "Net-(Q1-ND1)") (class "Default")
      (node (ref "Q1") (pin "7") (pinfunction "ND1_7") (pintype "bidirectional"))
      (node (ref "Q1") (pin "8") (pinfunction "ND2_8") (pintype "bidirectional"))
      (node (ref "R13") (pin "2") (pinfunction "2_2") (pintype "passive"))
    )
    (net (code "40") (name "Net-(Q1-PG)") (class "Default")
      (node (ref "C20") (pin "1") (pinfunction "1_1") (pintype "passive"))
      (node (ref "Q1") (pin "4") (pinfunction "PG_4") (pintype "bidirectional"))
      (node (ref "R19") (pin "2") (pinfunction "2_2") (pintype "passive"))
      (node (ref "R3") (pin "2") (pinfunction "2_2") (pintype "passive"))
    )
    (net (code "41") (name "Net-(Q3-PG)") (class "Default")
      (node (ref "C10") (pin "1") (pinfunction "1_1") (pintype "passive"))
      (node (ref "Q3") (pin "4") (pinfunction "PG_4") (pintype "bidirectional"))
      (node (ref "R14") (pin "2") (pinfunction "2_2") (pintype "passive"))
      (node (ref "R2") (pin "2") (pinfunction "2_2") (pintype "passive"))
    )
    (net (code "42") (name "Net-(SAW1-IN)") (class "Default")
      (node (ref "SAW1") (pin "P$2") (pinfunction "IN_P$2") (pintype "bidirectional"))
      (node (ref "U2") (pin "7") (pinfunction "ANT_SW_OUT_7") (pintype "bidirectional"))
    )
    (net (code "43") (name "Net-(SAW1-OUT)") (class "Default")
      (node (ref "SAW1") (pin "P$4") (pinfunction "OUT_P$4") (pintype "bidirectional"))
      (node (ref "U2") (pin "11") (pinfunction "MIX_IN_11") (pintype "bidirectional"))
    )
    (net (code "44") (name "Net-(TCXO1-OUT)") (class "Default")
      (node (ref "C6") (pin "2") (pinfunction "2_2") (pintype "passive"))
      (node (ref "TCXO1") (pin "3") (pinfunction "OUT_3") (pintype "bidirectional"))
    )
    (net (code "45") (name "Net-(TCXO1-VDD)") (class "Default")
      (node (ref "C8") (pin "1") (pinfunction "1_1") (pintype "passive"))
      (node (ref "TCXO1") (pin "4") (pinfunction "VDD_4") (pintype "bidirectional"))
      (node (ref "U2") (pin "13") (pinfunction "VCC_TCXO_13") (pintype "bidirectional"))
    )
    (net (code "46") (name "Net-(U1G-DECOUPLE)") (class "Default")
      (node (ref "C11") (pin "1") (pinfunction "1_1") (pintype "passive"))
      (node (ref "U1") (pin "20") (pinfunction "DECOUPLE_20") (pintype "power_in"))
    )
    (net (code "47") (name "Net-(U2-ANT_BIAS)") (class "Default")
      (node (ref "C2") (pin "2") (pinfunction "2_2") (pintype "passive"))
      (node (ref "L1") (pin "1") (pinfunction "1_1") (pintype "passive"))
      (node (ref "U2") (pin "2") (pinfunction "ANT_BIAS_2") (pintype "bidirectional"))
    )
    (net (code "48") (name "Net-(U2-ANT_IN)") (class "Default")
      (node (ref "C1") (pin "1") (pinfunction "1_1") (pintype "passive"))
      (node (ref "U2") (pin "3") (pinfunction "ANT_IN_3") (pintype "bidirectional"))
    )
    (net (code "49") (name "Net-(U2-RVI)") (class "Default")
      (node (ref "R1") (pin "1") (pinfunction "1_1") (pintype "passive"))
      (node (ref "U2") (pin "12") (pinfunction "RVI_12") (pintype "bidirectional"))
    )
    (net (code "50") (name "Net-(U2-TCXO_IN)") (class "Default")
      (node (ref "C6") (pin "1") (pinfunction "1_1") (pintype "passive"))
      (node (ref "U2") (pin "15") (pinfunction "TCXO_IN_15") (pintype "bidirectional"))
    )
    (net (code "51") (name "Net-(U2-VAGC)") (class "Default")
      (node (ref "C3") (pin "2") (pinfunction "2_2") (pintype "passive"))
      (node (ref "U2") (pin "1") (pinfunction "VAGC_1") (pintype "bidirectional"))
    )
    (net (code "52") (name "Net-(U3-IO1)") (class "Default")
      (node (ref "J1") (pin "6") (pinfunction "D+_6") (pintype "passive"))
      (node (ref "J1") (pin "7") (pinfunction "D+_7") (pintype "passive"))
      (node (ref "R12") (pin "2") (pinfunction "2_2") (pintype "passive"))
      (node (ref "U3") (pin "P$2") (pinfunction "IO1_P$2") (pintype "bidirectional"))
    )
    (net (code "53") (name "Net-(U3-IO2)") (class "Default")
      (node (ref "J1") (pin "5") (pinfunction "D-_5") (pintype "passive"))
      (node (ref "J1") (pin "8") (pinfunction "D-_8") (pintype "passive"))
      (node (ref "R11") (pin "2") (pinfunction "2_2") (pintype "passive"))
      (node (ref "U3") (pin "P$3") (pinfunction "IO2_P$3") (pintype "bidirectional"))
    )
    (net (code "54") (name "Net-(U3-VCC)") (class "Default")
      (node (ref "J1") (pin "11") (pinfunction "VBUS_11") (pintype "power_in"))
      (node (ref "J1") (pin "2") (pinfunction "VBUS_2") (pintype "power_in"))
      (node (ref "L2") (pin "1") (pinfunction "1_1") (pintype "passive"))
      (node (ref "U3") (pin "P$4") (pinfunction "VCC_P$4") (pintype "bidirectional"))
    )
    (net (code "55") (name "unconnected-(J1-SBU1-Pad10)") (class "Default")
      (node (ref "J1") (pin "10") (pinfunction "SBU1_10") (pintype "passive"))
    )
    (net (code "56") (name "unconnected-(J1-SBU2-Pad4)") (class "Default")
      (node (ref "J1") (pin "4") (pinfunction "SBU2_4") (pintype "passive"))
    )
    (net (code "57") (name "unconnected-(J2-PAD1-PadNC1)") (class "Default")
      (node (ref "J2") (pin "NC1") (pinfunction "PAD1_NC1") (pintype "bidirectional"))
    )
    (net (code "58") (name "unconnected-(J2-PAD2-PadNC2)") (class "Default")
      (node (ref "J2") (pin "NC2") (pinfunction "PAD2_NC2") (pintype "bidirectional"))
    )
    (net (code "59") (name "unconnected-(U1B-PB13{slash}HFXTAL_P{slash}LEUART0_TX#1{slash}USART0_CLK#4,5-Pad12)") (class "Default")
      (node (ref "U1") (pin "12") (pinfunction "PB13/HFXTAL_P/LEUART0_TX#1/USART0_CLK#4,5_12") (pintype "bidirectional"))
    )
    (net (code "60") (name "unconnected-(U2-ANT_DET-Pad8)") (class "Default")
      (node (ref "U2") (pin "8") (pinfunction "ANT_DET_8") (pintype "bidirectional"))
    )
    (net (code "61") (name "unconnected-(U2-LNA_IN-Pad4)") (class "Default")
      (node (ref "U2") (pin "4") (pinfunction "LNA_IN_4") (pintype "bidirectional"))
    )
    (net (code "62") (name "unconnected-(U2-MAG-Pad19)") (class "Default")
      (node (ref "U2") (pin "19") (pinfunction "MAG_19") (pintype "bidirectional"))
    )
  )
)
